# Board_ConnectionsSchDoc.net
KiCad netlist of a schematic drawn in Altium Designer
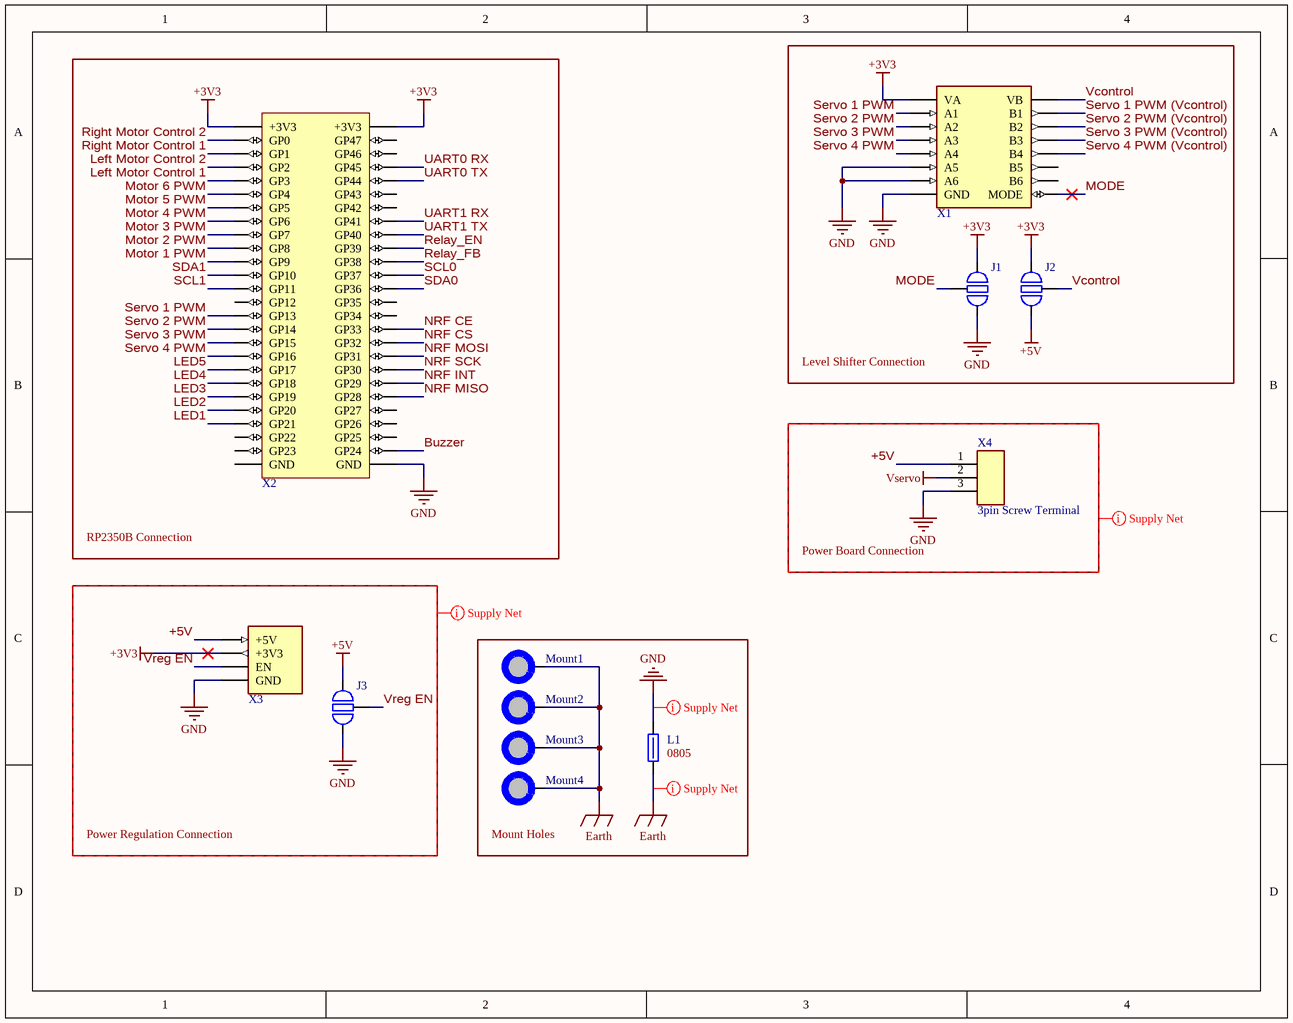
[diagram p0: Board ConnectionsSchDoc.SchDoc]

(export (version "E")
  (design (tool "Eeschema 10.0.6"))
  (components
    (comp (ref "J1")
      (value "[Jumper] Thru-Hole 3pin")
      (footprint "[Jumper] Thru-Hole 3pin")
      (libsource (lib "") (part "[Jumper] Thru-Hole 3pin_1"))
    )
    (comp (ref "J2")
      (value "[Jumper] Thru-Hole 3pin")
      (footprint "[Jumper] Thru-Hole 3pin")
      (libsource (lib "Misc Components") (part "[Jumper] Thru-Hole 3pin"))
    )
    (comp (ref "J3")
      (value "[Jumper] Thru-Hole 3pin")
      (footprint "[Jumper] Thru-Hole 3pin")
      (libsource (lib "Misc Components") (part "[Jumper] Thru-Hole 3pin"))
    )
    (comp (ref "L1")
      (value "652-MH2029-300Y")
      (footprint "[Ferrite] SMD 0805")
      (fields (field (name "SIZE PACKAGE") "0805"))
      (libsource (lib "Ferrite Beads") (part "[Ferrite] SMD 0805 3A 30ohm"))
    )
    (comp (ref "Mount1")
      (value "M3 Mount Hole")
      (footprint "[Mount] M3 Mount Hole")
      (description "Place at least 4.5mm from board edge. Plated.")
      (libsource (lib "RADM Connectors") (part "[Mount] M3 Mount Hole"))
    )
    (comp (ref "Mount2")
      (value "M3 Mount Hole")
      (footprint "[Mount] M3 Mount Hole")
      (description "Place at least 4.5mm from board edge. Plated.")
      (libsource (lib "RADM Connectors") (part "[Mount] M3 Mount Hole"))
    )
    (comp (ref "Mount3")
      (value "M3 Mount Hole")
      (footprint "[Mount] M3 Mount Hole")
      (description "Place at least 4.5mm from board edge. Plated.")
      (libsource (lib "RADM Connectors") (part "[Mount] M3 Mount Hole"))
    )
    (comp (ref "Mount4")
      (value "M3 Mount Hole")
      (footprint "[Mount] M3 Mount Hole")
      (description "Place at least 4.5mm from board edge. Plated.")
      (libsource (lib "RADM Connectors") (part "[Mount] M3 Mount Hole"))
    )
    (comp (ref "X1")
      (value "[Level Shifter] MC14504BDTR2G Breakout")
      (footprint "[Level Shifter] MC14504BDTR2G Breakout")
      (description "Custom MIL Part")
      (libsource (lib "Devices") (part "[Level Shifter] MC14504BDTR2G Breakout"))
    )
    (comp (ref "X2")
      (value "RP2350")
      (footprint "[Pi] RP2350B Breakout")
      (description "Custom MIL Part")
      (libsource (lib "Devices") (part "[Pi] RP2350B Breakout"))
    )
    (comp (ref "X3")
      (value "[Reg] 3V3 Linear Reg Breakout")
      (footprint "[Reg] 3V3 Linear Reg Breakout")
      (description "Custom MIL Part")
      (libsource (lib "Devices") (part "[Reg] 3V3 Linear Reg Breakout"))
    )
    (comp (ref "X4")
      (value "3pin Screw Terminal")
      (footprint "[Screw Terminal] 3pin 5mm")
      (libsource (lib "RADM Connectors") (part "[Screw Terminal] 3pin"))
    )
  )
  (nets
    (net (code "1") (name "+3V3") (class "Default")
      (node (ref "J1") (pin "1") (pintype "passive"))
      (node (ref "J2") (pin "1") (pintype "passive"))
      (node (ref "X1") (pin "1") (pinfunction "VA_1") (pintype "power_in"))
      (node (ref "X2") (pin "1") (pinfunction "+3V3_1") (pintype "power_in"))
      (node (ref "X2") (pin "52") (pinfunction "+3V3_52") (pintype "power_in"))
      (node (ref "X3") (pin "2") (pinfunction "+3V3_2") (pintype "output"))
    )
    (net (code "2") (name "+5V") (class "Default")
      (node (ref "J2") (pin "3") (pintype "passive"))
      (node (ref "J3") (pin "1") (pintype "passive"))
      (node (ref "X3") (pin "1") (pinfunction "+5V_1") (pintype "input"))
      (node (ref "X4") (pin "1") (pintype "power_in"))
    )
    (net (code "3") (name "/Buzzer") (class "Default")
      (node (ref "X2") (pin "28") (pinfunction "GP24_28") (pintype "bidirectional"))
    )
    (net (code "4") (name "/LED1") (class "Default")
      (node (ref "X2") (pin "23") (pinfunction "GP21_23") (pintype "bidirectional"))
    )
    (net (code "5") (name "/LED2") (class "Default")
      (node (ref "X2") (pin "22") (pinfunction "GP20_22") (pintype "bidirectional"))
    )
    (net (code "6") (name "/LED3") (class "Default")
      (node (ref "X2") (pin "21") (pinfunction "GP19_21") (pintype "bidirectional"))
    )
    (net (code "7") (name "/LED4") (class "Default")
      (node (ref "X2") (pin "20") (pinfunction "GP18_20") (pintype "bidirectional"))
    )
    (net (code "8") (name "/LED5") (class "Default")
      (node (ref "X2") (pin "19") (pinfunction "GP17_19") (pintype "bidirectional"))
    )
    (net (code "9") (name "/Left Motor Control 1") (class "Default")
      (node (ref "X2") (pin "5") (pinfunction "GP3_5") (pintype "bidirectional"))
    )
    (net (code "10") (name "/Left Motor Control 2") (class "Default")
      (node (ref "X2") (pin "4") (pinfunction "GP2_4") (pintype "bidirectional"))
    )
    (net (code "11") (name "/MODE") (class "Default")
      (node (ref "J1") (pin "2") (pinfunction "Common_2") (pintype "power_in"))
      (node (ref "X1") (pin "9") (pinfunction "MODE_9") (pintype "bidirectional"))
    )
    (net (code "12") (name "/Motor 1 PWM") (class "Default")
      (node (ref "X2") (pin "11") (pinfunction "GP9_11") (pintype "bidirectional"))
    )
    (net (code "13") (name "/Motor 2 PWM") (class "Default")
      (node (ref "X2") (pin "10") (pinfunction "GP8_10") (pintype "bidirectional"))
    )
    (net (code "14") (name "/Motor 3 PWM") (class "Default")
      (node (ref "X2") (pin "9") (pinfunction "GP7_9") (pintype "bidirectional"))
    )
    (net (code "15") (name "/Motor 4 PWM") (class "Default")
      (node (ref "X2") (pin "8") (pinfunction "GP6_8") (pintype "bidirectional"))
    )
    (net (code "16") (name "/Motor 5 PWM") (class "Default")
      (node (ref "X2") (pin "7") (pinfunction "GP5_7") (pintype "bidirectional"))
    )
    (net (code "17") (name "/Motor 6 PWM") (class "Default")
      (node (ref "X2") (pin "6") (pinfunction "GP4_6") (pintype "bidirectional"))
    )
    (net (code "18") (name "/NRF CE") (class "Default")
      (node (ref "X2") (pin "37") (pinfunction "GP33_37") (pintype "bidirectional"))
    )
    (net (code "19") (name "/NRF CS") (class "Default")
      (node (ref "X2") (pin "36") (pinfunction "GP32_36") (pintype "bidirectional"))
    )
    (net (code "20") (name "/NRF INT") (class "Default")
      (node (ref "X2") (pin "33") (pinfunction "GP29_33") (pintype "bidirectional"))
    )
    (net (code "21") (name "/NRF MISO") (class "Default")
      (node (ref "X2") (pin "32") (pinfunction "GP28_32") (pintype "bidirectional"))
    )
    (net (code "22") (name "/NRF MOSI") (class "Default")
      (node (ref "X2") (pin "35") (pinfunction "GP31_35") (pintype "bidirectional"))
    )
    (net (code "23") (name "/NRF SCK") (class "Default")
      (node (ref "X2") (pin "34") (pinfunction "GP30_34") (pintype "bidirectional"))
    )
    (net (code "24") (name "/Relay_EN") (class "Default")
      (node (ref "X2") (pin "43") (pinfunction "GP39_43") (pintype "bidirectional"))
    )
    (net (code "25") (name "/Relay_FB") (class "Default")
      (node (ref "X2") (pin "42") (pinfunction "GP38_42") (pintype "bidirectional"))
    )
    (net (code "26") (name "/Right Motor Control 1") (class "Default")
      (node (ref "X2") (pin "3") (pinfunction "GP1_3") (pintype "bidirectional"))
    )
    (net (code "27") (name "/Right Motor Control 2") (class "Default")
      (node (ref "X2") (pin "2") (pinfunction "GP0_2") (pintype "bidirectional"))
    )
    (net (code "28") (name "/SCL0") (class "Default")
      (node (ref "X2") (pin "41") (pinfunction "GP37_41") (pintype "bidirectional"))
    )
    (net (code "29") (name "/SCL1") (class "Default")
      (node (ref "X2") (pin "13") (pinfunction "GP11_13") (pintype "bidirectional"))
    )
    (net (code "30") (name "/SDA0") (class "Default")
      (node (ref "X2") (pin "40") (pinfunction "GP36_40") (pintype "bidirectional"))
    )
    (net (code "31") (name "/SDA1") (class "Default")
      (node (ref "X2") (pin "12") (pinfunction "GP10_12") (pintype "bidirectional"))
    )
    (net (code "32") (name "/Servo 1 PWM") (class "Default")
      (node (ref "X1") (pin "2") (pinfunction "A1_2") (pintype "input"))
      (node (ref "X2") (pin "15") (pinfunction "GP13_15") (pintype "bidirectional"))
    )
    (net (code "33") (name "/Servo 1 PWM (Vcontrol)") (class "Default")
      (node (ref "X1") (pin "15") (pinfunction "B1_15") (pintype "output"))
    )
    (net (code "34") (name "/Servo 2 PWM") (class "Default")
      (node (ref "X1") (pin "3") (pinfunction "A2_3") (pintype "input"))
      (node (ref "X2") (pin "16") (pinfunction "GP14_16") (pintype "bidirectional"))
    )
    (net (code "35") (name "/Servo 2 PWM (Vcontrol)") (class "Default")
      (node (ref "X1") (pin "14") (pinfunction "B2_14") (pintype "output"))
    )
    (net (code "36") (name "/Servo 3 PWM") (class "Default")
      (node (ref "X1") (pin "4") (pinfunction "A3_4") (pintype "input"))
      (node (ref "X2") (pin "17") (pinfunction "GP15_17") (pintype "bidirectional"))
    )
    (net (code "37") (name "/Servo 3 PWM (Vcontrol)") (class "Default")
      (node (ref "X1") (pin "13") (pinfunction "B3_13") (pintype "output"))
    )
    (net (code "38") (name "/Servo 4 PWM") (class "Default")
      (node (ref "X1") (pin "5") (pinfunction "A4_5") (pintype "input"))
      (node (ref "X2") (pin "18") (pinfunction "GP16_18") (pintype "bidirectional"))
    )
    (net (code "39") (name "/Servo 4 PWM (Vcontrol)") (class "Default")
      (node (ref "X1") (pin "12") (pinfunction "B4_12") (pintype "output"))
    )
    (net (code "40") (name "/UART0 RX") (class "Default")
      (node (ref "X2") (pin "49") (pinfunction "GP45_49") (pintype "bidirectional"))
    )
    (net (code "41") (name "/UART0 TX") (class "Default")
      (node (ref "X2") (pin "48") (pinfunction "GP44_48") (pintype "bidirectional"))
    )
    (net (code "42") (name "/UART1 RX") (class "Default")
      (node (ref "X2") (pin "45") (pinfunction "GP41_45") (pintype "bidirectional"))
    )
    (net (code "43") (name "/UART1 TX") (class "Default")
      (node (ref "X2") (pin "44") (pinfunction "GP40_44") (pintype "bidirectional"))
    )
    (net (code "44") (name "/Vcontrol") (class "Default")
      (node (ref "J2") (pin "2") (pinfunction "Common_2") (pintype "power_in"))
      (node (ref "X1") (pin "16") (pinfunction "VB_16") (pintype "power_in"))
    )
    (net (code "45") (name "/Vreg EN") (class "Default")
      (node (ref "J3") (pin "2") (pinfunction "Common_2") (pintype "power_in"))
      (node (ref "X3") (pin "3") (pinfunction "EN_3") (pintype "passive"))
    )
    (net (code "46") (name "Earth") (class "Default")
      (node (ref "L1") (pin "1") (pinfunction "1_1") (pintype "passive"))
      (node (ref "Mount1") (pin "1") (pintype "power_in"))
      (node (ref "Mount2") (pin "1") (pintype "power_in"))
      (node (ref "Mount3") (pin "1") (pintype "power_in"))
      (node (ref "Mount4") (pin "1") (pintype "power_in"))
    )
    (net (code "47") (name "GND") (class "Default")
      (node (ref "J1") (pin "3") (pintype "passive"))
      (node (ref "J3") (pin "3") (pintype "passive"))
      (node (ref "L1") (pin "2") (pinfunction "2_2") (pintype "passive"))
      (node (ref "X1") (pin "6") (pinfunction "A5_6") (pintype "input"))
      (node (ref "X1") (pin "7") (pinfunction "A6_7") (pintype "input"))
      (node (ref "X1") (pin "8") (pinfunction "GND_8") (pintype "power_in"))
      (node (ref "X2") (pin "27") (pinfunction "GND_27") (pintype "power_in"))
      (node (ref "X3") (pin "4") (pinfunction "GND_4") (pintype "passive"))
      (node (ref "X4") (pin "3") (pintype "power_in"))
    )
    (net (code "48") (name "Vservo") (class "Default") (node (ref "X4") (pin "2") (pintype "power_in")))
    (net (code "49") (name "unconnected-(X1-B5-Pad11)") (class "Default")
      (node (ref "X1") (pin "11") (pinfunction "B5_11") (pintype "output"))
    )
    (net (code "50") (name "unconnected-(X1-B6-Pad10)") (class "Default")
      (node (ref "X1") (pin "10") (pinfunction "B6_10") (pintype "output"))
    )
    (net (code "51") (name "unconnected-(X2-GND-Pad26)") (class "Default")
      (node (ref "X2") (pin "26") (pinfunction "GND_26") (pintype "power_in"))
    )
    (net (code "52") (name "unconnected-(X2-GP12-Pad14)") (class "Default")
      (node (ref "X2") (pin "14") (pinfunction "GP12_14") (pintype "bidirectional"))
    )
    (net (code "53") (name "unconnected-(X2-GP22-Pad24)") (class "Default")
      (node (ref "X2") (pin "24") (pinfunction "GP22_24") (pintype "bidirectional"))
    )
    (net (code "54") (name "unconnected-(X2-GP23-Pad25)") (class "Default")
      (node (ref "X2") (pin "25") (pinfunction "GP23_25") (pintype "bidirectional"))
    )
    (net (code "55") (name "unconnected-(X2-GP25-Pad29)") (class "Default")
      (node (ref "X2") (pin "29") (pinfunction "GP25_29") (pintype "bidirectional"))
    )
    (net (code "56") (name "unconnected-(X2-GP26-Pad30)") (class "Default")
      (node (ref "X2") (pin "30") (pinfunction "GP26_30") (pintype "bidirectional"))
    )
    (net (code "57") (name "unconnected-(X2-GP27-Pad31)") (class "Default")
      (node (ref "X2") (pin "31") (pinfunction "GP27_31") (pintype "bidirectional"))
    )
    (net (code "58") (name "unconnected-(X2-GP34-Pad38)") (class "Default")
      (node (ref "X2") (pin "38") (pinfunction "GP34_38") (pintype "bidirectional"))
    )
    (net (code "59") (name "unconnected-(X2-GP35-Pad39)") (class "Default")
      (node (ref "X2") (pin "39") (pinfunction "GP35_39") (pintype "bidirectional"))
    )
    (net (code "60") (name "unconnected-(X2-GP42-Pad46)") (class "Default")
      (node (ref "X2") (pin "46") (pinfunction "GP42_46") (pintype "bidirectional"))
    )
    (net (code "61") (name "unconnected-(X2-GP43-Pad47)") (class "Default")
      (node (ref "X2") (pin "47") (pinfunction "GP43_47") (pintype "bidirectional"))
    )
    (net (code "62") (name "unconnected-(X2-GP46-Pad50)") (class "Default")
      (node (ref "X2") (pin "50") (pinfunction "GP46_50") (pintype "bidirectional"))
    )
    (net (code "63") (name "unconnected-(X2-GP47-Pad51)") (class "Default")
      (node (ref "X2") (pin "51") (pinfunction "GP47_51") (pintype "bidirectional"))
    )
  )
)
